# MCU_64.net
KiCad netlist of a schematic drawn in Altium Designer
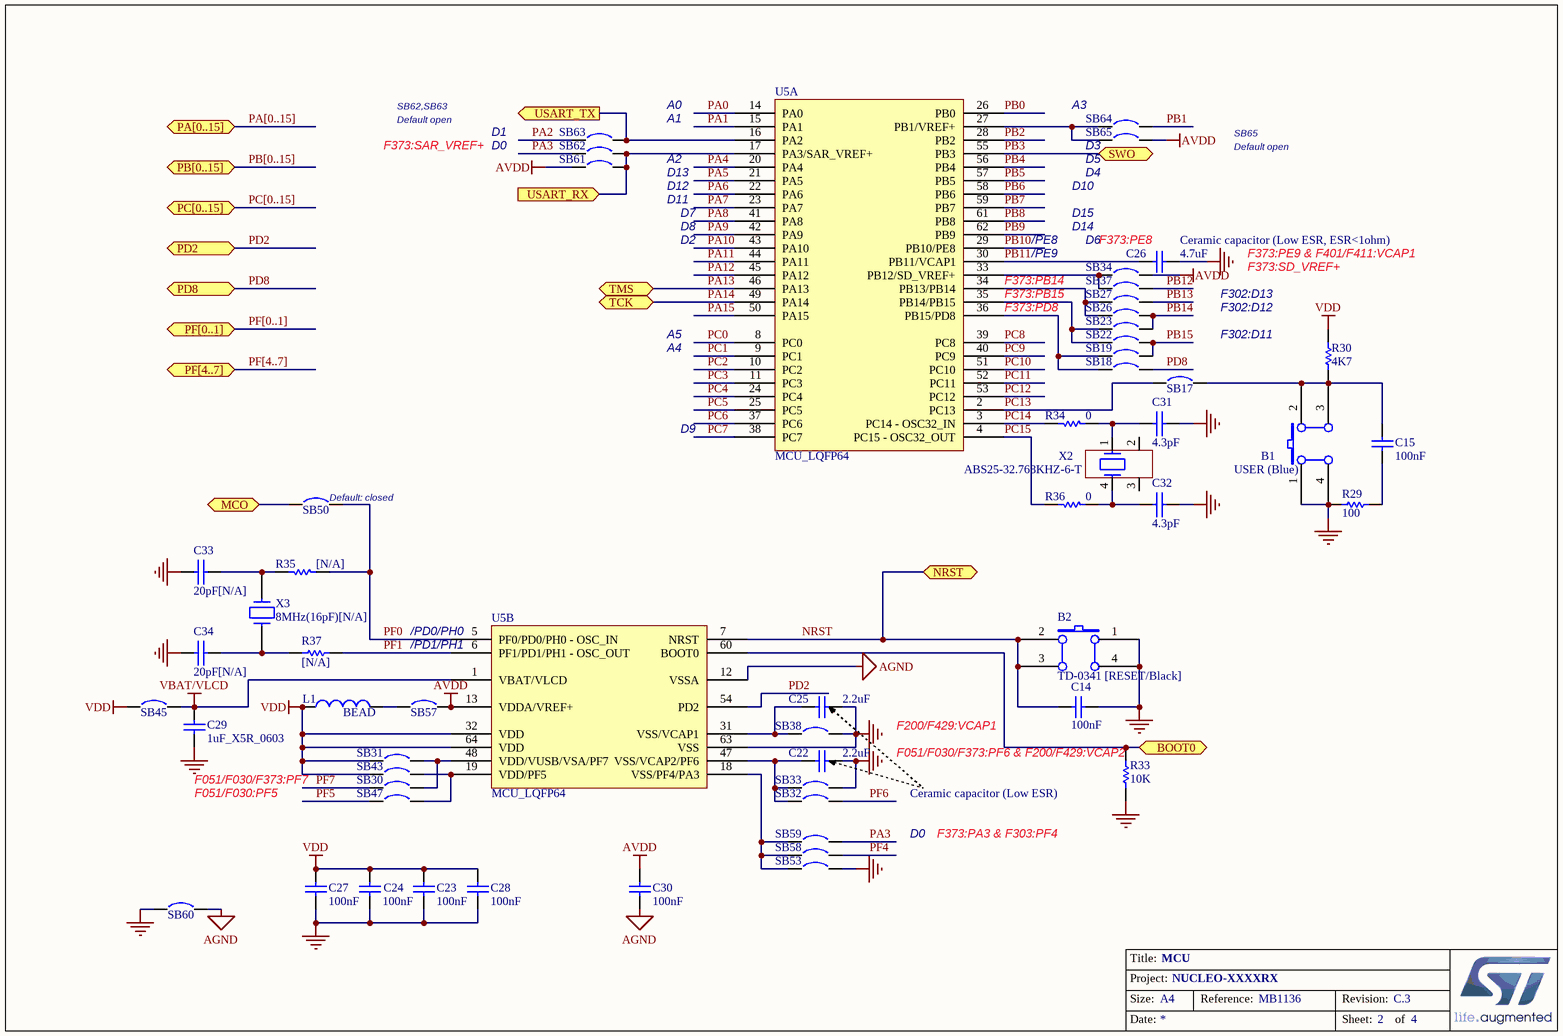
[diagram p0: MCU_64.SchDoc]

(export (version "E")
  (design (tool "Eeschema 10.0.6"))
  (components
    (comp (ref "B1")
      (value "USER (Blue)")
      (footprint "PB10")
      (description "SE PUSHBUTTON")
      (libsource (lib "Documents") (part "SW PUSHBUTTON"))
    )
    (comp (ref "B2")
      (value "TD-0341 [RESET/Black]")
      (footprint "PB10")
      (description "SE PUSHBUTTON")
      (libsource (lib "Documents") (part "SW PUSHBUTTON"))
    )
    (comp (ref "C14")
      (value "100nF")
      (footprint "0603C")
      (description "Capacitor")
      (fields (field (name "PUBLISHER") "Altium Limited"))
      (libsource (lib "Miscellaneous Devices") (part "CAP"))
    )
    (comp (ref "C15")
      (value "100nF")
      (footprint "0603C")
      (description "Capacitor")
      (fields (field (name "PUBLISHER") "Altium Limited"))
      (libsource (lib "Miscellaneous Devices") (part "CAP"))
    )
    (comp (ref "C22")
      (value "2.2uF")
      (footprint "TAN-A")
      (description "Capacitor,2.2uF,16V, X7R,10%,0805,YAGEO")
      (libsource (lib "MCD_TOOLS") (part "Cap_2.2uF_X7R_10%_0805"))
    )
    (comp (ref "C23")
      (value "100nF")
      (footprint "0603C")
      (description "Capacitor")
      (fields (field (name "PUBLISHER") "Altium Limited"))
      (libsource (lib "Miscellaneous Devices") (part "Cap"))
    )
    (comp (ref "C24")
      (value "100nF")
      (footprint "0603C")
      (description "Capacitor")
      (fields (field (name "PUBLISHER") "Altium Limited"))
      (libsource (lib "Miscellaneous Devices") (part "Cap"))
    )
    (comp (ref "C25")
      (value "2.2uF")
      (footprint "TAN-A")
      (description "Capacitor,2.2uF,16V, X7R,10%,0805,YAGEO")
      (libsource (lib "MCD_TOOLS") (part "Cap_2.2uF_X7R_10%_0805"))
    )
    (comp (ref "C26")
      (value "4.7uF")
      (footprint "TAN-A")
      (description "Capacitor,2.2uF,16V, X7R,10%,0805,YAGEO")
      (libsource (lib "MCD_TOOLS") (part "Cap_2.2uF_X7R_10%_0805"))
    )
    (comp (ref "C27")
      (value "100nF")
      (footprint "0603C")
      (description "Capacitor")
      (fields (field (name "PUBLISHER") "Altium Limited"))
      (libsource (lib "Miscellaneous Devices") (part "Cap"))
    )
    (comp (ref "C28")
      (value "100nF")
      (footprint "0603C")
      (description "Capacitor")
      (fields (field (name "PUBLISHER") "Altium Limited"))
      (libsource (lib "Miscellaneous Devices") (part "Cap"))
    )
    (comp (ref "C29")
      (value "1uF_X5R_0603")
      (footprint "0603C")
      (description "0603  X5R 1µF")
      (fields (field (name "TOLERANCE") "10%"))
      (libsource (lib "MB963_1") (part "CAP SMD 0603  X5R 1µF 25V 10%"))
    )
    (comp (ref "C30")
      (value "100nF")
      (footprint "0603C")
      (description "Capacitor")
      (fields (field (name "PUBLISHER") "Altium Limited"))
      (libsource (lib "Miscellaneous Devices") (part "Cap"))
    )
    (comp (ref "C31")
      (value "4.3pF")
      (footprint "0603C")
      (description "Capacitor")
      (libsource (lib "") (part "CAP_1"))
    )
    (comp (ref "C32")
      (value "4.3pF")
      (footprint "0603C")
      (description "Capacitor")
      (libsource (lib "") (part "CAP_1"))
    )
    (comp (ref "C33")
      (value "20pF[N/A]")
      (footprint "0603C")
      (description "Capacitor")
      (libsource (lib "*") (part "CAP"))
    )
    (comp (ref "C34")
      (value "20pF[N/A]")
      (footprint "0603C")
      (description "Capacitor")
      (libsource (lib "*") (part "CAP"))
    )
    (comp (ref "L1")
      (value "BEAD")
      (footprint "0603L")
      (description "Inductor")
      (fields (field (name "PUBLISHER") "Altium Limited"))
      (libsource (lib "Miscellaneous Devices") (part "Inductor"))
    )
    (comp (ref "R29")
      (value "100")
      (footprint "0603R")
      (description "Resistor")
      (fields (field (name "PUBLISHER") "Altium Limited"))
      (libsource (lib "Miscellaneous Devices") (part "Res1"))
    )
    (comp (ref "R30")
      (value "4K7")
      (footprint "0603R")
      (description "Resistor")
      (fields (field (name "PUBLISHER") "Altium Limited"))
      (libsource (lib "Miscellaneous Devices") (part "res1"))
    )
    (comp (ref "R33")
      (value "10K")
      (footprint "0603R")
      (description "Resistor")
      (fields (field (name "PUBLISHER") "Altium Limited"))
      (libsource (lib "Miscellaneous Devices") (part "res1"))
    )
    (comp (ref "R34")
      (value "0")
      (footprint "0603R")
      (description "Resistor")
      (fields (field (name "PUBLISHER") "Altium Limited"))
      (libsource (lib "") (part "Res1_1"))
    )
    (comp (ref "R35")
      (value "[N/A]")
      (footprint "0603R")
      (description "Resistor")
      (fields (field (name "PUBLISHER") "Altium Limited"))
      (libsource (lib "") (part "Res1_1"))
    )
    (comp (ref "R36")
      (value "0")
      (footprint "0603R")
      (description "Resistor")
      (fields (field (name "PUBLISHER") "Altium Limited"))
      (libsource (lib "") (part "Res1_1"))
    )
    (comp (ref "R37")
      (value "[N/A]")
      (footprint "0603R")
      (description "Resistor")
      (fields (field (name "PUBLISHER") "Altium Limited"))
      (libsource (lib "Miscellaneous Devices") (part "Res1"))
    )
    (comp (ref "SB17")
      (value "Circuit Breaker")
      (footprint "JP2_SMD")
      (fields (field (name "PUBLISHER") "Altium Limited"))
      (libsource (lib "MCD_TOOLS") (part "Circuit Breaker"))
    )
    (comp (ref "SB18")
      (value "Circuit Breaker")
      (footprint "JP2_SMD")
      (fields (field (name "PUBLISHER") "Altium Limited"))
      (libsource (lib "MCD_TOOLS") (part "Circuit Breaker"))
    )
    (comp (ref "SB19")
      (value "Circuit Breaker")
      (footprint "JP2_SMD")
      (fields (field (name "PUBLISHER") "Altium Limited"))
      (libsource (lib "MCD_TOOLS") (part "Circuit Breaker"))
    )
    (comp (ref "SB22")
      (value "Circuit Breaker")
      (footprint "JP2_SMD")
      (fields (field (name "PUBLISHER") "Altium Limited"))
      (libsource (lib "MCD_TOOLS") (part "Circuit Breaker"))
    )
    (comp (ref "SB23")
      (value "Circuit Breaker")
      (footprint "JP2_SMD")
      (fields (field (name "PUBLISHER") "Altium Limited"))
      (libsource (lib "MCD_TOOLS") (part "Circuit Breaker"))
    )
    (comp (ref "SB26")
      (value "Circuit Breaker")
      (footprint "JP2_SMD")
      (fields (field (name "PUBLISHER") "Altium Limited"))
      (libsource (lib "MCD_TOOLS") (part "Circuit Breaker"))
    )
    (comp (ref "SB27")
      (value "Circuit Breaker")
      (footprint "JP2_SMD")
      (fields (field (name "PUBLISHER") "Altium Limited"))
      (libsource (lib "MCD_TOOLS") (part "Circuit Breaker"))
    )
    (comp (ref "SB30")
      (value "Circuit Breaker")
      (footprint "JP2_SMD")
      (fields (field (name "PUBLISHER") "Altium Limited"))
      (libsource (lib "MCD_TOOLS") (part "Circuit Breaker"))
    )
    (comp (ref "SB31")
      (value "Circuit Breaker")
      (footprint "JP2_SMD")
      (fields (field (name "PUBLISHER") "Altium Limited"))
      (libsource (lib "MCD_TOOLS") (part "Circuit Breaker"))
    )
    (comp (ref "SB32")
      (value "Circuit Breaker")
      (footprint "JP2_SMD")
      (fields (field (name "PUBLISHER") "Altium Limited"))
      (libsource (lib "MCD_TOOLS") (part "Circuit Breaker"))
    )
    (comp (ref "SB33")
      (value "Circuit Breaker")
      (footprint "JP2_SMD")
      (fields (field (name "PUBLISHER") "Altium Limited"))
      (libsource (lib "MCD_TOOLS") (part "Circuit Breaker"))
    )
    (comp (ref "SB34")
      (value "Circuit Breaker")
      (footprint "JP2_SMD")
      (fields (field (name "PUBLISHER") "Altium Limited"))
      (libsource (lib "MCD_TOOLS") (part "Circuit Breaker"))
    )
    (comp (ref "SB37")
      (value "Circuit Breaker")
      (footprint "JP2_SMD")
      (fields (field (name "PUBLISHER") "Altium Limited"))
      (libsource (lib "MCD_TOOLS") (part "Circuit Breaker"))
    )
    (comp (ref "SB38")
      (value "Circuit Breaker")
      (footprint "JP2_SMD")
      (fields (field (name "PUBLISHER") "Altium Limited"))
      (libsource (lib "MCD_TOOLS") (part "Circuit Breaker"))
    )
    (comp (ref "SB43")
      (value "Circuit Breaker")
      (footprint "JP2_SMD")
      (fields (field (name "PUBLISHER") "Altium Limited"))
      (libsource (lib "MCD_TOOLS") (part "Circuit Breaker"))
    )
    (comp (ref "SB45")
      (value "Circuit Breaker")
      (footprint "JP2_SMD")
      (fields (field (name "PUBLISHER") "Altium Limited"))
      (libsource (lib "MCD_TOOLS") (part "Circuit Breaker"))
    )
    (comp (ref "SB47")
      (value "Circuit Breaker")
      (footprint "JP2_SMD")
      (fields (field (name "PUBLISHER") "Altium Limited"))
      (libsource (lib "MCD_TOOLS") (part "Circuit Breaker"))
    )
    (comp (ref "SB50")
      (value "Circuit Breaker")
      (footprint "JP2_SMD")
      (fields (field (name "PUBLISHER") "Altium Limited"))
      (libsource (lib "MCD_TOOLS") (part "Circuit Breaker"))
    )
    (comp (ref "SB53")
      (value "Circuit Breaker")
      (footprint "JP2_SMD")
      (fields (field (name "PUBLISHER") "Altium Limited"))
      (libsource (lib "MCD_TOOLS") (part "Circuit Breaker"))
    )
    (comp (ref "SB57")
      (value "Circuit Breaker")
      (footprint "JP2_SMD")
      (fields (field (name "PUBLISHER") "Altium Limited"))
      (libsource (lib "MCD_TOOLS") (part "Circuit Breaker"))
    )
    (comp (ref "SB58")
      (value "Circuit Breaker")
      (footprint "JP2_SMD")
      (fields (field (name "PUBLISHER") "Altium Limited"))
      (libsource (lib "MCD_TOOLS") (part "Circuit Breaker"))
    )
    (comp (ref "SB59")
      (value "Circuit Breaker")
      (footprint "JP2_SMD")
      (fields (field (name "PUBLISHER") "Altium Limited"))
      (libsource (lib "MCD_TOOLS") (part "Circuit Breaker"))
    )
    (comp (ref "SB60")
      (value "Circuit Breaker")
      (footprint "JP2_SMD")
      (fields (field (name "PUBLISHER") "Altium Limited"))
      (libsource (lib "MCD_TOOLS") (part "Circuit Breaker"))
    )
    (comp (ref "SB61")
      (value "Circuit Breaker")
      (footprint "JP2_SMD")
      (fields (field (name "PUBLISHER") "Altium Limited"))
      (libsource (lib "MCD_TOOLS") (part "Circuit Breaker"))
    )
    (comp (ref "SB62")
      (value "Circuit Breaker")
      (footprint "JP2_SMD")
      (fields (field (name "PUBLISHER") "Altium Limited"))
      (libsource (lib "MCD_TOOLS") (part "Circuit Breaker"))
    )
    (comp (ref "SB63")
      (value "Circuit Breaker")
      (footprint "JP2_SMD")
      (fields (field (name "PUBLISHER") "Altium Limited"))
      (libsource (lib "MCD_TOOLS") (part "Circuit Breaker"))
    )
    (comp (ref "SB64")
      (value "Circuit Breaker")
      (footprint "JP2_SMD")
      (fields (field (name "PUBLISHER") "Altium Limited"))
      (libsource (lib "MCD_TOOLS") (part "Circuit Breaker"))
    )
    (comp (ref "SB65")
      (value "Circuit Breaker")
      (footprint "JP2_SMD")
      (fields (field (name "PUBLISHER") "Altium Limited"))
      (libsource (lib "MCD_TOOLS") (part "Circuit Breaker"))
    )
    (comp (ref "U5")
      (value "MCU_LQFP64")
      (footprint "LQFP64")
      (libsource (lib "Nucleo_64") (part "MCU_LQFP64"))
    )
    (comp (ref "X2")
      (value "ABS25-32.768KHZ-6-T")
      (footprint "XTAL_4SM_8X3R8")
      (libsource (lib "*") (part "MC306"))
    )
    (comp (ref "X3")
      (value "8MHz(16pF)[N/A]")
      (footprint "XTAL1")
      (description "Crystal")
      (libsource (lib "*") (part "CRYSTAL"))
    )
  )
  (nets
    (net (code "1") (name "/BOOT0") (class "Default")
      (node (ref "R33") (pin "1") (pinfunction "1_1") (pintype "passive"))
      (node (ref "U5") (pin "60") (pinfunction "BOOT0_60") (pintype "passive"))
    )
    (net (code "2") (name "/MCO") (class "Default")
      (node (ref "SB50") (pin "1") (pinfunction "1_1") (pintype "passive"))
    )
    (net (code "3") (name "/NRST") (class "Default")
      (node (ref "B2") (pin "2") (pinfunction "B0_2") (pintype "passive"))
      (node (ref "B2") (pin "3") (pinfunction "B1_3") (pintype "passive"))
      (node (ref "C14") (pin "2") (pinfunction "2_2") (pintype "passive"))
      (node (ref "U5") (pin "7") (pinfunction "NRST_7") (pintype "passive"))
    )
    (net (code "4") (name "/PA0") (class "Default")
      (node (ref "U5") (pin "14") (pinfunction "PA0_14") (pintype "passive"))
    )
    (net (code "5") (name "/PA1") (class "Default")
      (node (ref "U5") (pin "15") (pinfunction "PA1_15") (pintype "passive"))
    )
    (net (code "6") (name "/PA2") (class "Default")
      (node (ref "SB63") (pin "1") (pinfunction "1_1") (pintype "passive"))
    )
    (net (code "7") (name "/PA3") (class "Default")
      (node (ref "SB59") (pin "2") (pinfunction "2_2") (pintype "passive"))
      (node (ref "SB62") (pin "1") (pinfunction "1_1") (pintype "passive"))
    )
    (net (code "8") (name "/PA4") (class "Default")
      (node (ref "U5") (pin "20") (pinfunction "PA4_20") (pintype "passive"))
    )
    (net (code "9") (name "/PA5") (class "Default")
      (node (ref "U5") (pin "21") (pinfunction "PA5_21") (pintype "passive"))
    )
    (net (code "10") (name "/PA6") (class "Default")
      (node (ref "U5") (pin "22") (pinfunction "PA6_22") (pintype "passive"))
    )
    (net (code "11") (name "/PA7") (class "Default")
      (node (ref "U5") (pin "23") (pinfunction "PA7_23") (pintype "passive"))
    )
    (net (code "12") (name "/PA8") (class "Default")
      (node (ref "U5") (pin "41") (pinfunction "PA8_41") (pintype "passive"))
    )
    (net (code "13") (name "/PA9") (class "Default")
      (node (ref "U5") (pin "42") (pinfunction "PA9_42") (pintype "passive"))
    )
    (net (code "14") (name "/PA10") (class "Default")
      (node (ref "U5") (pin "43") (pinfunction "PA10_43") (pintype "passive"))
    )
    (net (code "15") (name "/PA11") (class "Default")
      (node (ref "U5") (pin "44") (pinfunction "PA11_44") (pintype "passive"))
    )
    (net (code "16") (name "/PA12") (class "Default")
      (node (ref "U5") (pin "45") (pinfunction "PA12_45") (pintype "passive"))
    )
    (net (code "17") (name "/PA13") (class "Default")
      (node (ref "U5") (pin "46") (pinfunction "PA13_46") (pintype "passive"))
    )
    (net (code "18") (name "/PA14") (class "Default")
      (node (ref "U5") (pin "49") (pinfunction "PA14_49") (pintype "passive"))
    )
    (net (code "19") (name "/PA15") (class "Default")
      (node (ref "U5") (pin "50") (pinfunction "PA15_50") (pintype "passive"))
    )
    (net (code "21") (name "/PB0") (class "Default")
      (node (ref "U5") (pin "26") (pinfunction "PB0_26") (pintype "passive"))
    )
    (net (code "22") (name "/PB1") (class "Default")
      (node (ref "SB64") (pin "2") (pinfunction "2_2") (pintype "passive"))
    )
    (net (code "23") (name "/PB2") (class "Default")
      (node (ref "U5") (pin "28") (pinfunction "PB2_28") (pintype "passive"))
    )
    (net (code "24") (name "/PB3") (class "Default")
      (node (ref "U5") (pin "55") (pinfunction "PB3_55") (pintype "passive"))
    )
    (net (code "25") (name "/PB4") (class "Default")
      (node (ref "U5") (pin "56") (pinfunction "PB4_56") (pintype "passive"))
    )
    (net (code "26") (name "/PB5") (class "Default")
      (node (ref "U5") (pin "57") (pinfunction "PB5_57") (pintype "passive"))
    )
    (net (code "27") (name "/PB6") (class "Default")
      (node (ref "U5") (pin "58") (pinfunction "PB6_58") (pintype "passive"))
    )
    (net (code "28") (name "/PB7") (class "Default")
      (node (ref "U5") (pin "59") (pinfunction "PB7_59") (pintype "passive"))
    )
    (net (code "29") (name "/PB8") (class "Default")
      (node (ref "U5") (pin "61") (pinfunction "PB8_61") (pintype "passive"))
    )
    (net (code "30") (name "/PB9") (class "Default")
      (node (ref "U5") (pin "62") (pinfunction "PB9_62") (pintype "passive"))
    )
    (net (code "31") (name "/PB10") (class "Default")
      (node (ref "U5") (pin "29") (pinfunction "PB10/PE8_29") (pintype "passive"))
    )
    (net (code "32") (name "/PB11") (class "Default")
      (node (ref "C26") (pin "1") (pinfunction "1_1") (pintype "passive"))
      (node (ref "U5") (pin "30") (pinfunction "PB11/VCAP1_30") (pintype "passive"))
    )
    (net (code "33") (name "/PB12") (class "Default")
      (node (ref "SB37") (pin "2") (pinfunction "2_2") (pintype "passive"))
    )
    (net (code "34") (name "/PB13") (class "Default")
      (node (ref "SB27") (pin "2") (pinfunction "2_2") (pintype "passive"))
    )
    (net (code "35") (name "/PB14") (class "Default")
      (node (ref "SB23") (pin "2") (pinfunction "2_2") (pintype "passive"))
      (node (ref "SB26") (pin "2") (pinfunction "2_2") (pintype "passive"))
    )
    (net (code "36") (name "/PB15") (class "Default")
      (node (ref "SB19") (pin "2") (pinfunction "2_2") (pintype "passive"))
      (node (ref "SB22") (pin "2") (pinfunction "2_2") (pintype "passive"))
    )
    (net (code "38") (name "/PC0") (class "Default")
      (node (ref "U5") (pin "8") (pinfunction "PC0_8") (pintype "passive"))
    )
    (net (code "39") (name "/PC1") (class "Default")
      (node (ref "U5") (pin "9") (pinfunction "PC1_9") (pintype "passive"))
    )
    (net (code "40") (name "/PC2") (class "Default")
      (node (ref "U5") (pin "10") (pinfunction "PC2_10") (pintype "passive"))
    )
    (net (code "41") (name "/PC3") (class "Default")
      (node (ref "U5") (pin "11") (pinfunction "PC3_11") (pintype "passive"))
    )
    (net (code "42") (name "/PC4") (class "Default")
      (node (ref "U5") (pin "24") (pinfunction "PC4_24") (pintype "passive"))
    )
    (net (code "43") (name "/PC5") (class "Default")
      (node (ref "U5") (pin "25") (pinfunction "PC5_25") (pintype "passive"))
    )
    (net (code "44") (name "/PC6") (class "Default")
      (node (ref "U5") (pin "37") (pinfunction "PC6_37") (pintype "passive"))
    )
    (net (code "45") (name "/PC7") (class "Default")
      (node (ref "U5") (pin "38") (pinfunction "PC7_38") (pintype "passive"))
    )
    (net (code "46") (name "/PC8") (class "Default")
      (node (ref "U5") (pin "39") (pinfunction "PC8_39") (pintype "passive"))
    )
    (net (code "47") (name "/PC9") (class "Default")
      (node (ref "U5") (pin "40") (pinfunction "PC9_40") (pintype "passive"))
    )
    (net (code "48") (name "/PC10") (class "Default")
      (node (ref "U5") (pin "51") (pinfunction "PC10_51") (pintype "passive"))
    )
    (net (code "49") (name "/PC11") (class "Default")
      (node (ref "U5") (pin "52") (pinfunction "PC11_52") (pintype "passive"))
    )
    (net (code "50") (name "/PC12") (class "Default")
      (node (ref "U5") (pin "53") (pinfunction "PC12_53") (pintype "passive"))
    )
    (net (code "51") (name "/PC13") (class "Default")
      (node (ref "SB17") (pin "1") (pinfunction "1_1") (pintype "passive"))
      (node (ref "U5") (pin "2") (pinfunction "PC13_2") (pintype "passive"))
    )
    (net (code "52") (name "/PC14") (class "Default")
      (node (ref "R34") (pin "2") (pinfunction "2_2") (pintype "passive"))
      (node (ref "U5") (pin "3") (pinfunction "PC14_-_OSC32_IN_3") (pintype "passive"))
    )
    (net (code "53") (name "/PC15") (class "Default")
      (node (ref "R36") (pin "2") (pinfunction "2_2") (pintype "passive"))
      (node (ref "U5") (pin "4") (pinfunction "PC15_-_OSC32_OUT_4") (pintype "passive"))
    )
    (net (code "55") (name "/PD2") (class "Default")
      (node (ref "U5") (pin "54") (pinfunction "PD2_54") (pintype "passive"))
    )
    (net (code "56") (name "/PD8") (class "Default")
      (node (ref "SB18") (pin "2") (pinfunction "2_2") (pintype "passive"))
    )
    (net (code "57") (name "/PF0") (class "Default")
      (node (ref "R35") (pin "1") (pinfunction "1_1") (pintype "passive"))
      (node (ref "SB50") (pin "2") (pinfunction "2_2") (pintype "passive"))
      (node (ref "U5") (pin "5") (pinfunction "PF0/PD0/PH0_-_OSC_IN_5") (pintype "passive"))
    )
    (net (code "58") (name "/PF1") (class "Default")
      (node (ref "R37") (pin "1") (pinfunction "1_1") (pintype "passive"))
      (node (ref "U5") (pin "6") (pinfunction "PF1/PD1/PH1_-_OSC_OUT_6") (pintype "passive"))
    )
    (net (code "59") (name "/PF4") (class "Default")
      (node (ref "SB58") (pin "2") (pinfunction "2_2") (pintype "passive"))
    )
    (net (code "60") (name "/PF5") (class "Default")
      (node (ref "SB47") (pin "1") (pinfunction "1_1") (pintype "passive"))
    )
    (net (code "61") (name "/PF6") (class "Default")
      (node (ref "SB32") (pin "2") (pinfunction "2_2") (pintype "passive"))
    )
    (net (code "62") (name "/PF7") (class "Default")
      (node (ref "SB30") (pin "1") (pinfunction "1_1") (pintype "passive"))
    )
    (net (code "65") (name "/USART_RX") (class "Default")
      (node (ref "SB61") (pin "2") (pinfunction "2_2") (pintype "passive"))
      (node (ref "SB62") (pin "2") (pinfunction "2_2") (pintype "passive"))
      (node (ref "U5") (pin "17") (pinfunction "PA3/SAR_VREF+_17") (pintype "passive"))
    )
    (net (code "66") (name "/USART_TX") (class "Default")
      (node (ref "SB63") (pin "2") (pinfunction "2_2") (pintype "passive"))
      (node (ref "U5") (pin "16") (pinfunction "PA2_16") (pintype "passive"))
    )
    (net (code "67") (name "AGND") (class "Default")
      (node (ref "C30") (pin "2") (pinfunction "2_2") (pintype "passive"))
      (node (ref "SB60") (pin "2") (pinfunction "2_2") (pintype "passive"))
      (node (ref "U5") (pin "12") (pinfunction "VSSA_12") (pintype "passive"))
    )
    (net (code "68") (name "AVDD") (class "Default")
      (node (ref "C30") (pin "1") (pinfunction "1_1") (pintype "passive"))
      (node (ref "SB34") (pin "2") (pinfunction "2_2") (pintype "passive"))
      (node (ref "SB57") (pin "2") (pinfunction "2_2") (pintype "passive"))
      (node (ref "SB61") (pin "1") (pinfunction "1_1") (pintype "passive"))
      (node (ref "SB65") (pin "2") (pinfunction "2_2") (pintype "passive"))
      (node (ref "U5") (pin "13") (pinfunction "VDDA/VREF+_13") (pintype "passive"))
    )
    (net (code "69") (name "GND") (class "Default")
      (node (ref "B1") (pin "1") (pinfunction "A0_1") (pintype "passive"))
      (node (ref "B1") (pin "4") (pinfunction "A1_4") (pintype "passive"))
      (node (ref "B2") (pin "1") (pinfunction "A0_1") (pintype "passive"))
      (node (ref "B2") (pin "4") (pinfunction "A1_4") (pintype "passive"))
      (node (ref "C14") (pin "1") (pinfunction "1_1") (pintype "passive"))
      (node (ref "C22") (pin "2") (pinfunction "2_2") (pintype "passive"))
      (node (ref "C23") (pin "2") (pinfunction "2_2") (pintype "passive"))
      (node (ref "C24") (pin "2") (pinfunction "2_2") (pintype "passive"))
      (node (ref "C25") (pin "2") (pinfunction "2_2") (pintype "passive"))
      (node (ref "C26") (pin "2") (pinfunction "2_2") (pintype "passive"))
      (node (ref "C27") (pin "2") (pinfunction "2_2") (pintype "passive"))
      (node (ref "C28") (pin "2") (pinfunction "2_2") (pintype "passive"))
      (node (ref "C29") (pin "2") (pinfunction "2_2") (pintype "passive"))
      (node (ref "C31") (pin "2") (pinfunction "2_2") (pintype "passive"))
      (node (ref "C32") (pin "2") (pinfunction "2_2") (pintype "passive"))
      (node (ref "C33") (pin "2") (pinfunction "2_2") (pintype "passive"))
      (node (ref "C34") (pin "2") (pinfunction "2_2") (pintype "passive"))
      (node (ref "R29") (pin "1") (pinfunction "1_1") (pintype "passive"))
      (node (ref "R33") (pin "2") (pinfunction "2_2") (pintype "passive"))
      (node (ref "SB33") (pin "2") (pinfunction "2_2") (pintype "passive"))
      (node (ref "SB38") (pin "2") (pinfunction "2_2") (pintype "passive"))
      (node (ref "SB53") (pin "2") (pinfunction "2_2") (pintype "passive"))
      (node (ref "SB60") (pin "1") (pinfunction "1_1") (pintype "passive"))
      (node (ref "U5") (pin "63") (pinfunction "VSS_63") (pintype "passive"))
    )
    (net (code "70") (name "Net-(B1-B0)") (class "Default")
      (node (ref "B1") (pin "2") (pinfunction "B0_2") (pintype "passive"))
      (node (ref "B1") (pin "3") (pinfunction "B1_3") (pintype "passive"))
      (node (ref "C15") (pin "2") (pinfunction "2_2") (pintype "passive"))
      (node (ref "R30") (pin "1") (pinfunction "1_1") (pintype "passive"))
      (node (ref "SB17") (pin "2") (pinfunction "2_2") (pintype "passive"))
    )
    (net (code "71") (name "Net-(C15-Pad1)") (class "Default")
      (node (ref "C15") (pin "1") (pinfunction "1_1") (pintype "passive"))
      (node (ref "R29") (pin "2") (pinfunction "2_2") (pintype "passive"))
    )
    (net (code "72") (name "Net-(C31-Pad1)") (class "Default")
      (node (ref "C31") (pin "1") (pinfunction "1_1") (pintype "passive"))
      (node (ref "R34") (pin "1") (pinfunction "1_1") (pintype "passive"))
      (node (ref "X2") (pin "1") (pinfunction "1_1") (pintype "passive"))
    )
    (net (code "73") (name "Net-(C32-Pad1)") (class "Default")
      (node (ref "C32") (pin "1") (pinfunction "1_1") (pintype "passive"))
      (node (ref "R36") (pin "1") (pinfunction "1_1") (pintype "passive"))
      (node (ref "X2") (pin "4") (pinfunction "4_4") (pintype "passive"))
    )
    (net (code "74") (name "Net-(C33-Pad1)") (class "Default")
      (node (ref "C33") (pin "1") (pinfunction "1_1") (pintype "passive"))
      (node (ref "R35") (pin "2") (pinfunction "2_2") (pintype "passive"))
      (node (ref "X3") (pin "2") (pinfunction "2_2") (pintype "passive"))
    )
    (net (code "75") (name "Net-(C34-Pad1)") (class "Default")
      (node (ref "C34") (pin "1") (pinfunction "1_1") (pintype "passive"))
      (node (ref "R37") (pin "2") (pinfunction "2_2") (pintype "passive"))
      (node (ref "X3") (pin "1") (pinfunction "1_1") (pintype "passive"))
    )
    (net (code "76") (name "Net-(L1-Pad2)") (class "Default")
      (node (ref "L1") (pin "2") (pinfunction "2_2") (pintype "passive"))
      (node (ref "SB57") (pin "1") (pinfunction "1_1") (pintype "passive"))
    )
    (net (code "77") (name "Net-(U5A-PB1{slash}VREF+)") (class "Default")
      (node (ref "SB64") (pin "1") (pinfunction "1_1") (pintype "passive"))
      (node (ref "SB65") (pin "1") (pinfunction "1_1") (pintype "passive"))
      (node (ref "U5") (pin "27") (pinfunction "PB1/VREF+_27") (pintype "passive"))
    )
    (net (code "78") (name "Net-(U5A-PB12{slash}SD_VREF+)") (class "Default")
      (node (ref "SB34") (pin "1") (pinfunction "1_1") (pintype "passive"))
      (node (ref "SB37") (pin "1") (pinfunction "1_1") (pintype "passive"))
      (node (ref "U5") (pin "33") (pinfunction "PB12/SD_VREF+_33") (pintype "passive"))
    )
    (net (code "79") (name "Net-(U5A-PB13{slash}PB14)") (class "Default")
      (node (ref "SB26") (pin "1") (pinfunction "1_1") (pintype "passive"))
      (node (ref "SB27") (pin "1") (pinfunction "1_1") (pintype "passive"))
      (node (ref "U5") (pin "34") (pinfunction "PB13/PB14_34") (pintype "passive"))
    )
    (net (code "80") (name "Net-(U5A-PB14{slash}PB15)") (class "Default")
      (node (ref "SB22") (pin "1") (pinfunction "1_1") (pintype "passive"))
      (node (ref "SB23") (pin "1") (pinfunction "1_1") (pintype "passive"))
      (node (ref "U5") (pin "35") (pinfunction "PB14/PB15_35") (pintype "passive"))
    )
    (net (code "81") (name "Net-(U5A-PB15{slash}PD8)") (class "Default")
      (node (ref "SB18") (pin "1") (pinfunction "1_1") (pintype "passive"))
      (node (ref "SB19") (pin "1") (pinfunction "1_1") (pintype "passive"))
      (node (ref "U5") (pin "36") (pinfunction "PB15/PD8_36") (pintype "passive"))
    )
    (net (code "82") (name "Net-(U5B-VDD{slash}PF5)") (class "Default")
      (node (ref "SB43") (pin "2") (pinfunction "2_2") (pintype "passive"))
      (node (ref "SB47") (pin "2") (pinfunction "2_2") (pintype "passive"))
      (node (ref "U5") (pin "19") (pinfunction "VDD/PF5_19") (pintype "passive"))
    )
    (net (code "83") (name "Net-(U5B-VDD{slash}VUSB{slash}VSA{slash}PF7)") (class "Default")
      (node (ref "SB30") (pin "2") (pinfunction "2_2") (pintype "passive"))
      (node (ref "SB31") (pin "2") (pinfunction "2_2") (pintype "passive"))
      (node (ref "U5") (pin "48") (pinfunction "VDD/VUSB/VSA/PF7_48") (pintype "passive"))
    )
    (net (code "84") (name "Net-(U5B-VSS{slash}PF4{slash}PA3)") (class "Default")
      (node (ref "SB53") (pin "1") (pinfunction "1_1") (pintype "passive"))
      (node (ref "SB58") (pin "1") (pinfunction "1_1") (pintype "passive"))
      (node (ref "SB59") (pin "1") (pinfunction "1_1") (pintype "passive"))
      (node (ref "U5") (pin "18") (pinfunction "VSS/PF4/PA3_18") (pintype "passive"))
    )
    (net (code "85") (name "Net-(U5B-VSS{slash}VCAP1)") (class "Default")
      (node (ref "C25") (pin "1") (pinfunction "1_1") (pintype "passive"))
      (node (ref "SB38") (pin "1") (pinfunction "1_1") (pintype "passive"))
      (node (ref "U5") (pin "31") (pinfunction "VSS/VCAP1_31") (pintype "passive"))
    )
    (net (code "86") (name "Net-(U5B-VSS{slash}VCAP2{slash}PF6)") (class "Default")
      (node (ref "C22") (pin "1") (pinfunction "1_1") (pintype "passive"))
      (node (ref "SB32") (pin "1") (pinfunction "1_1") (pintype "passive"))
      (node (ref "SB33") (pin "1") (pinfunction "1_1") (pintype "passive"))
      (node (ref "U5") (pin "47") (pinfunction "VSS/VCAP2/PF6_47") (pintype "passive"))
    )
    (net (code "87") (name "VBAT{slash}VLCD") (class "Default")
      (node (ref "C29") (pin "1") (pinfunction "1_1") (pintype "passive"))
      (node (ref "SB45") (pin "2") (pinfunction "2_2") (pintype "passive"))
      (node (ref "U5") (pin "1") (pinfunction "VBAT/VLCD_1") (pintype "passive"))
    )
    (net (code "88") (name "VDD") (class "Default")
      (node (ref "C23") (pin "1") (pinfunction "1_1") (pintype "passive"))
      (node (ref "C24") (pin "1") (pinfunction "1_1") (pintype "passive"))
      (node (ref "C27") (pin "1") (pinfunction "1_1") (pintype "passive"))
      (node (ref "C28") (pin "1") (pinfunction "1_1") (pintype "passive"))
      (node (ref "L1") (pin "1") (pinfunction "1_1") (pintype "passive"))
      (node (ref "R30") (pin "2") (pinfunction "2_2") (pintype "passive"))
      (node (ref "SB31") (pin "1") (pinfunction "1_1") (pintype "passive"))
      (node (ref "SB43") (pin "1") (pinfunction "1_1") (pintype "passive"))
      (node (ref "SB45") (pin "1") (pinfunction "1_1") (pintype "passive"))
      (node (ref "U5") (pin "32") (pinfunction "VDD_32") (pintype "passive"))
      (node (ref "U5") (pin "64") (pinfunction "VDD_64") (pintype "passive"))
    )
    (net (code "89") (name "unconnected-(X2-Pad2)") (class "Default")
      (node (ref "X2") (pin "2") (pinfunction "2_2") (pintype "passive"))
    )
    (net (code "90") (name "unconnected-(X2-Pad3)") (class "Default")
      (node (ref "X2") (pin "3") (pinfunction "3_3") (pintype "passive"))
    )
  )
)
